# PolarityProtection.net
KiCad netlist of a schematic drawn in Altium Designer
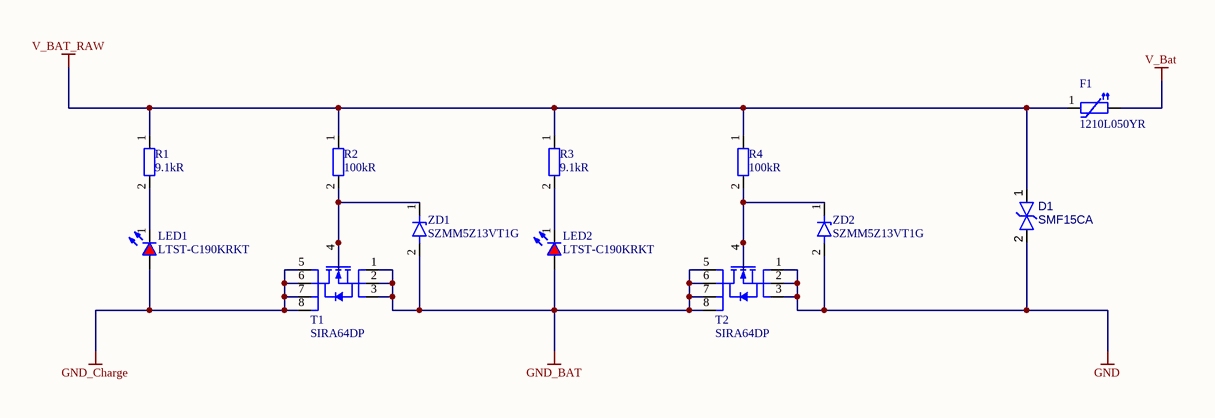
[diagram p0: PolarityProtection.SchDoc]

(export (version "E")
  (design (tool "Eeschema 10.0.6"))
  (components
    (comp (ref "D1")
      (value "SMF15CA")
      (footprint "SODFL370X110-2L")
      (description "TVS Diode, bidirectional, 15V, 8.2A, 200W, SOD-123FL-2")
      (libsource (lib "ZHAW on Altium 365") (part "D-TVS-AA-2"))
    )
    (comp (ref "F1")
      (value "1210L050YR")
      (footprint "FUSER3225X08L")
      (description "Resettable Fuse, Ihold 500mA, Itrip 1A, 13.2V, 1210")
      (libsource (lib "ZHAW on Altium 365") (part "RESFUSE-2"))
    )
    (comp (ref "LED1")
      (value "LTST-C190KRKT")
      (footprint "LEDSC160X80X80-2Lrd")
      (description "LED, Red, 20mA, 2.0V, 0603")
      (libsource (lib "ZHAW on Altium 365") (part "LED-RD-KA-2"))
    )
    (comp (ref "LED2")
      (value "LTST-C190KRKT")
      (footprint "LEDSC160X80X80-2Lrd")
      (description "LED, Red, 20mA, 2.0V, 0603")
      (libsource (lib "ZHAW on Altium 365") (part "LED-RD-KA-2"))
    )
    (comp (ref "R1")
      (value "9.1kR")
      (footprint "RESC1608X06L")
      (description "Res, 9.1kR, 1%, 0.1W, 0603")
      (fields (field (name "TOLERANCE") "1%") (field (name "POWER") "100mW"))
      (libsource (lib "ZHAW on Altium 365") (part "RES-2"))
    )
    (comp (ref "R2")
      (value "100kR")
      (footprint "RESC1608X06L")
      (description "Res, 100kR, 1%, 0.1W, 0603")
      (fields (field (name "TOLERANCE") "1%") (field (name "POWER") "100mW"))
      (libsource (lib "ZHAW on Altium 365") (part "RES-2"))
    )
    (comp (ref "R3")
      (value "9.1kR")
      (footprint "RESC1608X06L")
      (description "Res, 9.1kR, 1%, 0.1W, 0603")
      (fields (field (name "TOLERANCE") "1%") (field (name "POWER") "100mW"))
      (libsource (lib "ZHAW on Altium 365") (part "RES-2"))
    )
    (comp (ref "R4")
      (value "100kR")
      (footprint "RESC1608X06L")
      (description "Res, 100kR, 1%, 0.1W, 0603")
      (fields (field (name "TOLERANCE") "1%") (field (name "POWER") "100mW"))
      (libsource (lib "ZHAW on Altium 365") (part "RES-2"))
    )
    (comp (ref "T1")
      (value "SIRA64DP")
      (footprint "SON127P620X110-9T400X365L")
      (description "MOSFET N-Enh, 30V, 60A, 100Ap, 2.1mR, 27.8W, SO-8")
      (fields (field (name "POWER") "27.8W") (field (name "VOLTAGE") "30V"))
      (libsource (lib "ZHAW on Altium 365") (part "NEMOS-SSSGDDDD-8"))
    )
    (comp (ref "T2")
      (value "SIRA64DP")
      (footprint "SON127P620X110-9T400X365L")
      (description "MOSFET N-Enh, 30V, 60A, 100Ap, 2.1mR, 27.8W, SO-8")
      (fields (field (name "POWER") "27.8W") (field (name "VOLTAGE") "30V"))
      (libsource (lib "ZHAW on Altium 365") (part "NEMOS-SSSGDDDD-8"))
    )
    (comp (ref "ZD1")
      (value "SZMM5Z13VT1G")
      (footprint "SODFL160X70-2L")
      (description "Zener Diode, 13.25V±0.85V, 5mA, 30R, 500mW, SOD-523-2")
      (fields (field (name "VOLTAGE") "13.25V") (field (name "POWER") "500mW"))
      (libsource (lib "ZHAW on Altium 365") (part "D-Z-KA-2"))
    )
    (comp (ref "ZD2")
      (value "SZMM5Z13VT1G")
      (footprint "SODFL160X70-2L")
      (description "Zener Diode, 13.25V±0.85V, 5mA, 30R, 500mW, SOD-523-2")
      (fields (field (name "VOLTAGE") "13.25V") (field (name "POWER") "500mW"))
      (libsource (lib "ZHAW on Altium 365") (part "D-Z-KA-2"))
    )
  )
  (nets
    (net (code "1") (name "GND") (class "Default")
      (node (ref "D1") (pin "2") (pinfunction "A_2") (pintype "passive"))
      (node (ref "T2") (pin "1") (pinfunction "S_1") (pintype "passive"))
      (node (ref "T2") (pin "2") (pinfunction "S_2") (pintype "passive"))
      (node (ref "T2") (pin "3") (pinfunction "S_3") (pintype "passive"))
      (node (ref "ZD2") (pin "2") (pinfunction "Anode_2") (pintype "passive"))
    )
    (net (code "2") (name "GND_BAT") (class "Default")
      (node (ref "LED2") (pin "2") (pinfunction "A_2") (pintype "passive"))
      (node (ref "T1") (pin "1") (pinfunction "S_1") (pintype "passive"))
      (node (ref "T1") (pin "2") (pinfunction "S_2") (pintype "passive"))
      (node (ref "T1") (pin "3") (pinfunction "S_3") (pintype "passive"))
      (node (ref "T2") (pin "5") (pinfunction "D_5") (pintype "passive"))
      (node (ref "T2") (pin "6") (pinfunction "D_6") (pintype "passive"))
      (node (ref "T2") (pin "7") (pinfunction "D_7") (pintype "passive"))
      (node (ref "T2") (pin "8") (pinfunction "D_8") (pintype "passive"))
      (node (ref "ZD1") (pin "2") (pinfunction "Anode_2") (pintype "passive"))
    )
    (net (code "3") (name "GND_Charge") (class "Default")
      (node (ref "LED1") (pin "2") (pinfunction "A_2") (pintype "passive"))
      (node (ref "T1") (pin "5") (pinfunction "D_5") (pintype "passive"))
      (node (ref "T1") (pin "6") (pinfunction "D_6") (pintype "passive"))
      (node (ref "T1") (pin "7") (pinfunction "D_7") (pintype "passive"))
      (node (ref "T1") (pin "8") (pinfunction "D_8") (pintype "passive"))
    )
    (net (code "4") (name "Net-(LED1-K)") (class "Default")
      (node (ref "LED1") (pin "1") (pinfunction "K_1") (pintype "passive"))
      (node (ref "R1") (pin "2") (pinfunction "2_2") (pintype "passive"))
    )
    (net (code "5") (name "Net-(LED2-K)") (class "Default")
      (node (ref "LED2") (pin "1") (pinfunction "K_1") (pintype "passive"))
      (node (ref "R3") (pin "2") (pinfunction "2_2") (pintype "passive"))
    )
    (net (code "6") (name "Net-(T1-G)") (class "Default")
      (node (ref "R2") (pin "2") (pinfunction "2_2") (pintype "passive"))
      (node (ref "T1") (pin "4") (pinfunction "G_4") (pintype "passive"))
      (node (ref "ZD1") (pin "1") (pinfunction "Cathode_1") (pintype "passive"))
    )
    (net (code "7") (name "Net-(T2-G)") (class "Default")
      (node (ref "R4") (pin "2") (pinfunction "2_2") (pintype "passive"))
      (node (ref "T2") (pin "4") (pinfunction "G_4") (pintype "passive"))
      (node (ref "ZD2") (pin "1") (pinfunction "Cathode_1") (pintype "passive"))
    )
    (net (code "8") (name "V_BAT_RAW") (class "Default")
      (node (ref "D1") (pin "1") (pinfunction "A_1") (pintype "passive"))
      (node (ref "F1") (pin "1") (pinfunction "1_1") (pintype "passive"))
      (node (ref "R1") (pin "1") (pinfunction "1_1") (pintype "passive"))
      (node (ref "R2") (pin "1") (pinfunction "1_1") (pintype "passive"))
      (node (ref "R3") (pin "1") (pinfunction "1_1") (pintype "passive"))
      (node (ref "R4") (pin "1") (pinfunction "1_1") (pintype "passive"))
    )
    (net (code "9") (name "V_Bat") (class "Default")
      (node (ref "F1") (pin "2") (pinfunction "2_2") (pintype "passive"))
    )
  )
)
